# P05_Power.net
KiCad netlist of a schematic drawn in Altium Designer
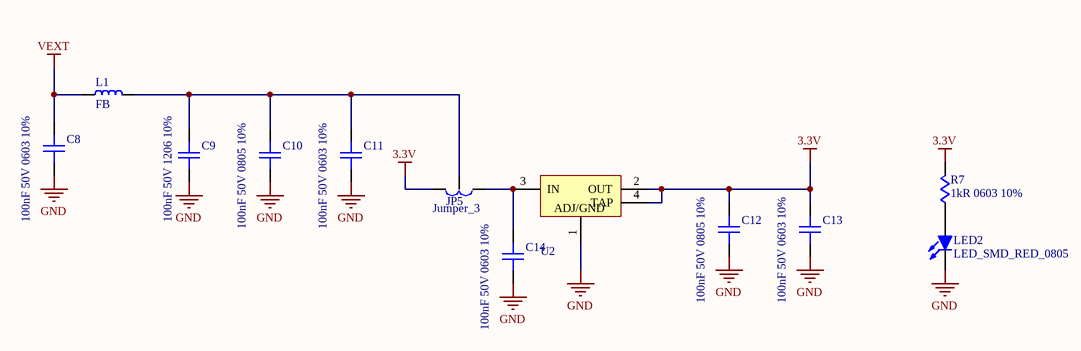
[diagram p0: P05_Power.SchDoc]

(export (version "E")
  (design (tool "Eeschema 10.0.6"))
  (components
    (comp (ref "C8")
      (value "100nF 50V 0603 10%")
      (footprint "CAPC-0603-M")
      (libsource (lib "esaltlib20") (part "CAP_SMD_0603"))
    )
    (comp (ref "C9")
      (value "100nF 50V 1206 10%")
      (footprint "CAPC-1206-M")
      (libsource (lib "esaltlib20") (part "CAP_SMD_1206"))
    )
    (comp (ref "C10")
      (value "100nF 50V 0805 10%")
      (footprint "CAPC-0805-M")
      (libsource (lib "esaltlib20") (part "CAP_SMD_0805"))
    )
    (comp (ref "C11")
      (value "100nF 50V 0603 10%")
      (footprint "CAPC-0603-M")
      (libsource (lib "esaltlib20") (part "CAP_SMD_0603"))
    )
    (comp (ref "C12")
      (value "100nF 50V 0805 10%")
      (footprint "CAPC-0805-M")
      (libsource (lib "esaltlib20") (part "CAP_SMD_0805"))
    )
    (comp (ref "C13")
      (value "100nF 50V 0603 10%")
      (footprint "CAPC-0603-M")
      (libsource (lib "esaltlib20") (part "CAP_SMD_0603"))
    )
    (comp (ref "C14")
      (value "100nF 50V 0603 10%")
      (footprint "CAPC-0603-M")
      (libsource (lib "esaltlib20") (part "CAP_SMD_0603"))
    )
    (comp (ref "JP5")
      (value "Jumper_3")
      (footprint "JMP_SMD_3")
      (libsource (lib "esaltlib20") (part "Jumper_3"))
    )
    (comp (ref "L1")
      (value "FB")
      (footprint "INDC-0805-M")
      (libsource (lib "esaltlib20") (part "IND_SMD_0805"))
    )
    (comp (ref "LED2")
      (value "LED_SMD_RED_0805")
      (footprint "LED-RED-0805-M")
      (libsource (lib "esaltlib20") (part "LED_SMD_RED_0805"))
    )
    (comp (ref "R7")
      (value "1kR 0603 10%")
      (footprint "RESC-0603-M")
      (libsource (lib "esaltlib20") (part "RES_SMD_0603"))
    )
    (comp (ref "U2")
      (value "LM1117_3.3V_SMD")
      (footprint "SOT223-4M")
      (libsource (lib "esaltlib20") (part "LM1117_3.3V_SMD"))
    )
  )
  (nets
    (net (code "1") (name "3.3V") (class "Default")
      (node (ref "C12") (pin "1") (pinfunction "1_1") (pintype "passive"))
      (node (ref "C13") (pin "1") (pinfunction "1_1") (pintype "passive"))
      (node (ref "JP5") (pin "3") (pinfunction "C_3") (pintype "passive"))
      (node (ref "R7") (pin "2") (pinfunction "B_2") (pintype "passive"))
      (node (ref "U2") (pin "2") (pinfunction "OUT_2") (pintype "passive"))
      (node (ref "U2") (pin "4") (pinfunction "TAP_4") (pintype "passive"))
    )
    (net (code "2") (name "GND") (class "Default")
      (node (ref "C10") (pin "2") (pinfunction "2_2") (pintype "passive"))
      (node (ref "C11") (pin "2") (pinfunction "2_2") (pintype "passive"))
      (node (ref "C12") (pin "2") (pinfunction "2_2") (pintype "passive"))
      (node (ref "C13") (pin "2") (pinfunction "2_2") (pintype "passive"))
      (node (ref "C14") (pin "2") (pinfunction "2_2") (pintype "passive"))
      (node (ref "C8") (pin "2") (pinfunction "2_2") (pintype "passive"))
      (node (ref "C9") (pin "2") (pinfunction "2_2") (pintype "passive"))
      (node (ref "LED2") (pin "2") (pinfunction "K_2") (pintype "passive"))
      (node (ref "U2") (pin "1") (pinfunction "ADJ/GND_1") (pintype "passive"))
    )
    (net (code "3") (name "Net-(JP5-A)") (class "Default")
      (node (ref "C14") (pin "1") (pinfunction "1_1") (pintype "passive"))
      (node (ref "JP5") (pin "1") (pinfunction "A_1") (pintype "passive"))
      (node (ref "U2") (pin "3") (pinfunction "IN_3") (pintype "passive"))
    )
    (net (code "4") (name "Net-(JP5-B)") (class "Default")
      (node (ref "C10") (pin "1") (pinfunction "1_1") (pintype "passive"))
      (node (ref "C11") (pin "1") (pinfunction "1_1") (pintype "passive"))
      (node (ref "C9") (pin "1") (pinfunction "1_1") (pintype "passive"))
      (node (ref "JP5") (pin "2") (pinfunction "B_2") (pintype "passive"))
      (node (ref "L1") (pin "2") (pinfunction "B_2") (pintype "passive"))
    )
    (net (code "5") (name "Net-(LED2-A)") (class "Default")
      (node (ref "LED2") (pin "1") (pinfunction "A_1") (pintype "passive"))
      (node (ref "R7") (pin "1") (pinfunction "A_1") (pintype "passive"))
    )
    (net (code "6") (name "VEXT") (class "Default")
      (node (ref "C8") (pin "1") (pinfunction "1_1") (pintype "passive"))
      (node (ref "L1") (pin "1") (pinfunction "A_1") (pintype "passive"))
    )
  )
)
